# Test_Points.net
KiCad netlist of a schematic drawn in Altium Designer
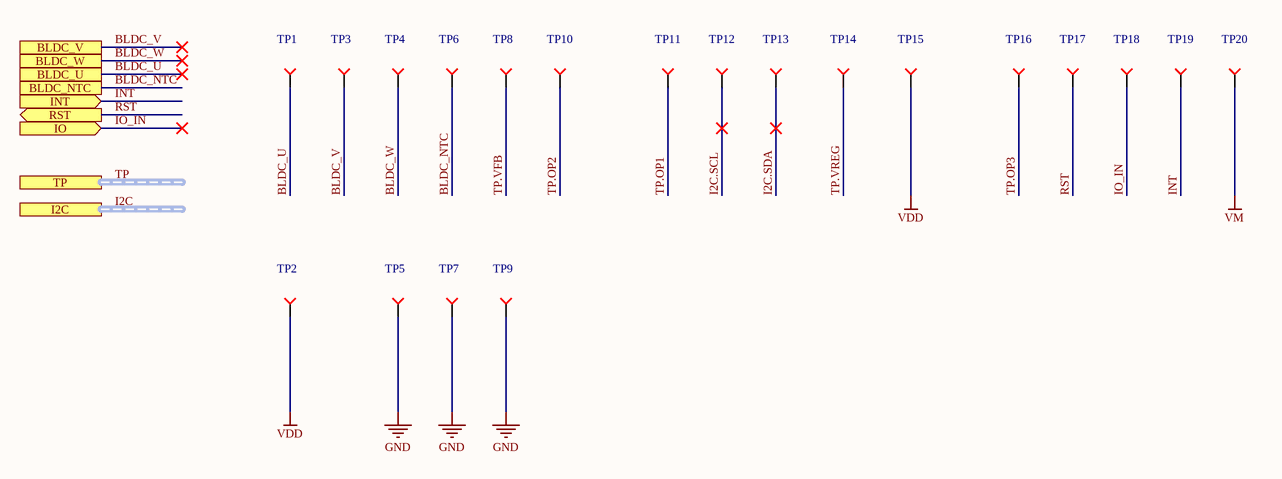
[diagram p0: Test_Points.SchDoc]

(export (version "E")
  (design (tool "Eeschema 10.0.6"))
  (components
    (comp (ref "TP1")
      (value "Test Point Pad")
      (footprint "Testpoint")
      (description "Test Point. There is nothing to buy or mount.")
      (libsource (lib "BLDC_Motor_Driver") (part "Test Point Pad"))
    )
    (comp (ref "TP2")
      (value "Test Point Pad")
      (footprint "Testpoint")
      (description "Test Point. There is nothing to buy or mount.")
      (libsource (lib "BLDC_Motor_Driver") (part "Test Point Pad"))
    )
    (comp (ref "TP3")
      (value "Test Point Pad")
      (footprint "Testpoint")
      (description "Test Point. There is nothing to buy or mount.")
      (libsource (lib "BLDC_Motor_Driver") (part "Test Point Pad"))
    )
    (comp (ref "TP4")
      (value "Test Point Pad")
      (footprint "Testpoint")
      (description "Test Point. There is nothing to buy or mount.")
      (libsource (lib "BLDC_Motor_Driver") (part "Test Point Pad"))
    )
    (comp (ref "TP5")
      (value "Test Point Pad")
      (footprint "Testpoint")
      (description "Test Point. There is nothing to buy or mount.")
      (libsource (lib "BLDC_Motor_Driver") (part "Test Point Pad"))
    )
    (comp (ref "TP6")
      (value "Test Point Pad")
      (footprint "Testpoint")
      (description "Test Point. There is nothing to buy or mount.")
      (libsource (lib "BLDC_Motor_Driver") (part "Test Point Pad"))
    )
    (comp (ref "TP7")
      (value "Test Point Pad")
      (footprint "Testpoint")
      (description "Test Point. There is nothing to buy or mount.")
      (libsource (lib "BLDC_Motor_Driver") (part "Test Point Pad"))
    )
    (comp (ref "TP8")
      (value "Test Point Pad")
      (footprint "Testpoint")
      (description "Test Point. There is nothing to buy or mount.")
      (libsource (lib "BLDC_Motor_Driver") (part "Test Point Pad"))
    )
    (comp (ref "TP9")
      (value "Test Point Pad")
      (footprint "Testpoint")
      (description "Test Point. There is nothing to buy or mount.")
      (libsource (lib "BLDC_Motor_Driver") (part "Test Point Pad"))
    )
    (comp (ref "TP10")
      (value "Test Point Pad")
      (footprint "Testpoint")
      (description "Test Point. There is nothing to buy or mount.")
      (libsource (lib "BLDC_Motor_Driver") (part "Test Point Pad"))
    )
    (comp (ref "TP11")
      (value "Test Point Pad")
      (footprint "Testpoint")
      (description "Test Point. There is nothing to buy or mount.")
      (libsource (lib "BLDC_Motor_Driver") (part "Test Point Pad"))
    )
    (comp (ref "TP12")
      (value "Test Point Pad")
      (footprint "Testpoint")
      (description "Test Point. There is nothing to buy or mount.")
      (libsource (lib "BLDC_Motor_Driver") (part "Test Point Pad"))
    )
    (comp (ref "TP13")
      (value "Test Point Pad")
      (footprint "Testpoint")
      (description "Test Point. There is nothing to buy or mount.")
      (libsource (lib "BLDC_Motor_Driver") (part "Test Point Pad"))
    )
    (comp (ref "TP14")
      (value "Test Point Pad")
      (footprint "Testpoint")
      (description "Test Point. There is nothing to buy or mount.")
      (libsource (lib "BLDC_Motor_Driver") (part "Test Point Pad"))
    )
    (comp (ref "TP15")
      (value "Test Point Pad")
      (footprint "Testpoint")
      (description "Test Point. There is nothing to buy or mount.")
      (libsource (lib "BLDC_Motor_Driver") (part "Test Point Pad"))
    )
    (comp (ref "TP16")
      (value "Test Point Pad")
      (footprint "Testpoint")
      (description "Test Point. There is nothing to buy or mount.")
      (libsource (lib "BLDC_Motor_Driver") (part "Test Point Pad"))
    )
    (comp (ref "TP17")
      (value "Test Point Pad")
      (footprint "Testpoint")
      (description "Test Point. There is nothing to buy or mount.")
      (libsource (lib "BLDC_Motor_Driver") (part "Test Point Pad"))
    )
    (comp (ref "TP18")
      (value "Test Point Pad")
      (footprint "Testpoint")
      (description "Test Point. There is nothing to buy or mount.")
      (libsource (lib "BLDC_Motor_Driver") (part "Test Point Pad"))
    )
    (comp (ref "TP19")
      (value "Test Point Pad")
      (footprint "Testpoint")
      (description "Test Point. There is nothing to buy or mount.")
      (libsource (lib "BLDC_Motor_Driver") (part "Test Point Pad"))
    )
    (comp (ref "TP20")
      (value "Test Point Pad")
      (footprint "Testpoint")
      (description "Test Point. There is nothing to buy or mount.")
      (libsource (lib "BLDC_Motor_Driver") (part "Test Point Pad"))
    )
  )
  (nets
    (net (code "3") (name "/BLDC_NTC") (class "Default")
      (node (ref "TP6") (pin "1") (pinfunction "1_1") (pintype "passive"))
    )
    (net (code "4") (name "/BLDC_U") (class "Default")
      (node (ref "TP1") (pin "1") (pinfunction "1_1") (pintype "passive+no_connect"))
    )
    (net (code "5") (name "/BLDC_V") (class "Default")
      (node (ref "TP3") (pin "1") (pinfunction "1_1") (pintype "passive"))
    )
    (net (code "6") (name "/BLDC_W") (class "Default")
      (node (ref "TP4") (pin "1") (pinfunction "1_1") (pintype "passive"))
    )
    (net (code "7") (name "/I2C.SCL") (class "Default")
      (node (ref "TP12") (pin "1") (pinfunction "1_1") (pintype "passive"))
    )
    (net (code "8") (name "/I2C.SDA") (class "Default")
      (node (ref "TP13") (pin "1") (pinfunction "1_1") (pintype "passive"))
    )
    (net (code "9") (name "/INT") (class "Default")
      (node (ref "TP19") (pin "1") (pinfunction "1_1") (pintype "passive"))
    )
    (net (code "10") (name "/IO_IN") (class "Default")
      (node (ref "TP18") (pin "1") (pinfunction "1_1") (pintype "passive+no_connect"))
    )
    (net (code "11") (name "/RST") (class "Default")
      (node (ref "TP17") (pin "1") (pinfunction "1_1") (pintype "passive"))
    )
    (net (code "12") (name "/TP.OP1") (class "Default")
      (node (ref "TP11") (pin "1") (pinfunction "1_1") (pintype "passive"))
    )
    (net (code "13") (name "/TP.OP2") (class "Default")
      (node (ref "TP10") (pin "1") (pinfunction "1_1") (pintype "passive"))
    )
    (net (code "14") (name "/TP.OP3") (class "Default")
      (node (ref "TP16") (pin "1") (pinfunction "1_1") (pintype "passive"))
    )
    (net (code "15") (name "/TP.VFB") (class "Default")
      (node (ref "TP8") (pin "1") (pinfunction "1_1") (pintype "passive"))
    )
    (net (code "16") (name "/TP.VREG") (class "Default")
      (node (ref "TP14") (pin "1") (pinfunction "1_1") (pintype "passive"))
    )
    (net (code "19") (name "GND") (class "Default")
      (node (ref "TP5") (pin "1") (pinfunction "1_1") (pintype "passive"))
      (node (ref "TP7") (pin "1") (pinfunction "1_1") (pintype "passive"))
      (node (ref "TP9") (pin "1") (pinfunction "1_1") (pintype "passive"))
    )
    (net (code "20") (name "VDD") (class "Default")
      (node (ref "TP15") (pin "1") (pinfunction "1_1") (pintype "passive"))
      (node (ref "TP2") (pin "1") (pinfunction "1_1") (pintype "passive"))
    )
    (net (code "21") (name "VM") (class "Default")
      (node (ref "TP20") (pin "1") (pinfunction "1_1") (pintype "passive"))
    )
  )
)
